# BATT_DISP.net
KiCad netlist of a schematic drawn in EAGLE
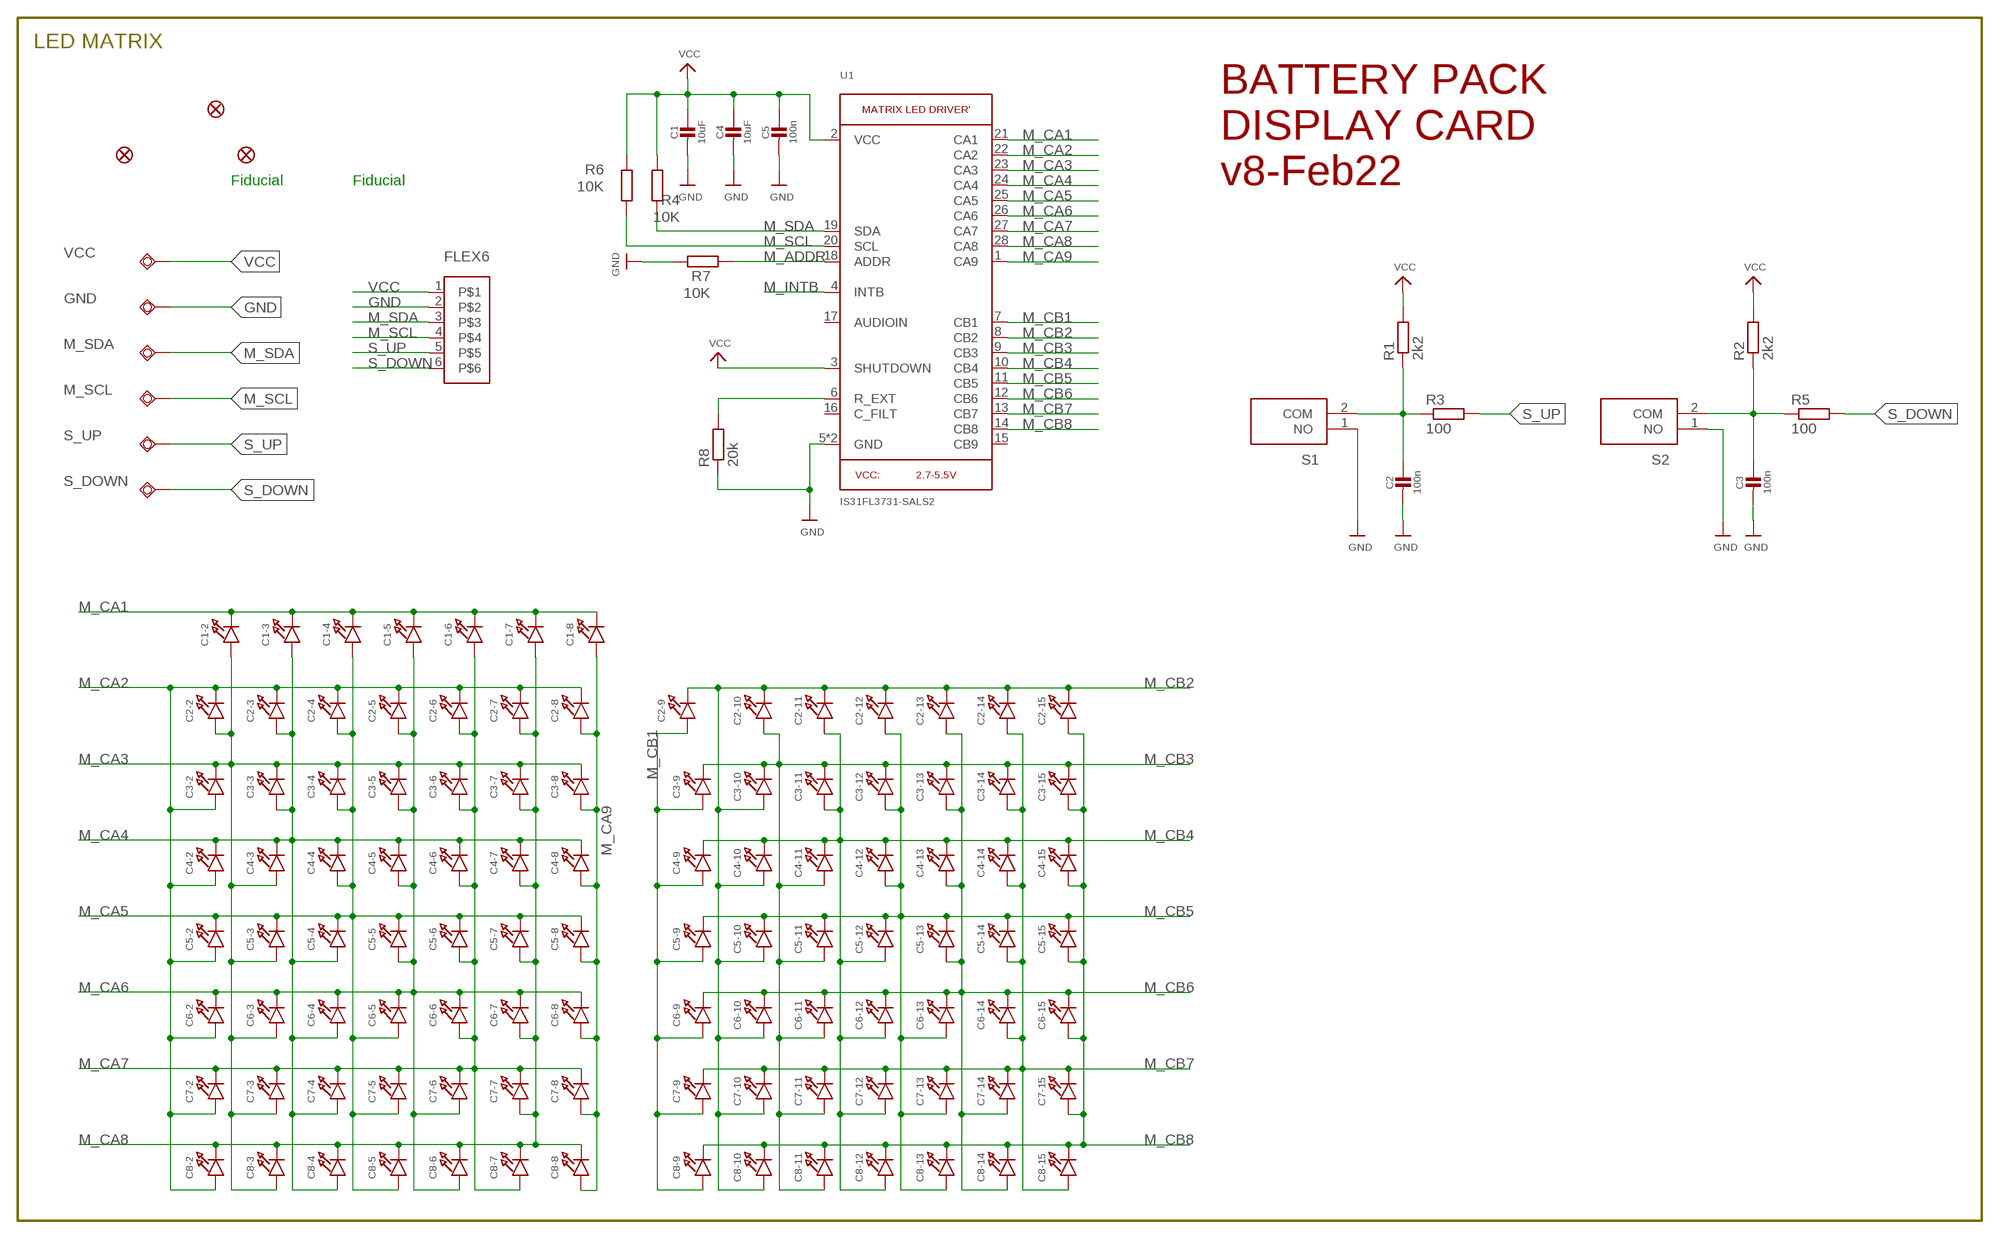
[diagram p0: schematic, sheet 1]

(export (version "E")
  (design (tool "Eeschema 10.0.6"))
  (components
    (comp (ref "C1")
      (value "10uF")
      (footprint "eagle-import:0805-NO")
      (libsource (lib "eagle-import") (part "CAP_CERAMIC0805-NOOUTLINE"))
    )
    (comp (ref "C1-2")
      (value "LED0402_NOOUTLINE")
      (footprint "eagle-import:CHIPLED_0402_NOOUTLINE")
      (libsource (lib "eagle-import") (part "LED0402_NOOUTLINE"))
    )
    (comp (ref "C1-3")
      (value "LED0402_NOOUTLINE")
      (footprint "eagle-import:CHIPLED_0402_NOOUTLINE")
      (libsource (lib "eagle-import") (part "LED0402_NOOUTLINE"))
    )
    (comp (ref "C1-4")
      (value "LED0402_NOOUTLINE")
      (footprint "eagle-import:CHIPLED_0402_NOOUTLINE")
      (libsource (lib "eagle-import") (part "LED0402_NOOUTLINE"))
    )
    (comp (ref "C1-5")
      (value "LED0402_NOOUTLINE")
      (footprint "eagle-import:CHIPLED_0402_NOOUTLINE")
      (libsource (lib "eagle-import") (part "LED0402_NOOUTLINE"))
    )
    (comp (ref "C1-6")
      (value "LED0402_NOOUTLINE")
      (footprint "eagle-import:CHIPLED_0402_NOOUTLINE")
      (libsource (lib "eagle-import") (part "LED0402_NOOUTLINE"))
    )
    (comp (ref "C1-7")
      (value "LED0402_NOOUTLINE")
      (footprint "eagle-import:CHIPLED_0402_NOOUTLINE")
      (libsource (lib "eagle-import") (part "LED0402_NOOUTLINE"))
    )
    (comp (ref "C1-8")
      (value "LED0402_NOOUTLINE")
      (footprint "eagle-import:CHIPLED_0402_NOOUTLINE")
      (libsource (lib "eagle-import") (part "LED0402_NOOUTLINE"))
    )
    (comp (ref "C2")
      (value "100n")
      (footprint "eagle-import:0805-NO")
      (libsource (lib "eagle-import") (part "CAP_CERAMIC0805-NOOUTLINE"))
    )
    (comp (ref "C2-2")
      (value "LED0402_NOOUTLINE")
      (footprint "eagle-import:CHIPLED_0402_NOOUTLINE")
      (libsource (lib "eagle-import") (part "LED0402_NOOUTLINE"))
    )
    (comp (ref "C2-3")
      (value "LED0402_NOOUTLINE")
      (footprint "eagle-import:CHIPLED_0402_NOOUTLINE")
      (libsource (lib "eagle-import") (part "LED0402_NOOUTLINE"))
    )
    (comp (ref "C2-4")
      (value "LED0402_NOOUTLINE")
      (footprint "eagle-import:CHIPLED_0402_NOOUTLINE")
      (libsource (lib "eagle-import") (part "LED0402_NOOUTLINE"))
    )
    (comp (ref "C2-5")
      (value "LED0402_NOOUTLINE")
      (footprint "eagle-import:CHIPLED_0402_NOOUTLINE")
      (libsource (lib "eagle-import") (part "LED0402_NOOUTLINE"))
    )
    (comp (ref "C2-6")
      (value "LED0402_NOOUTLINE")
      (footprint "eagle-import:CHIPLED_0402_NOOUTLINE")
      (libsource (lib "eagle-import") (part "LED0402_NOOUTLINE"))
    )
    (comp (ref "C2-7")
      (value "LED0402_NOOUTLINE")
      (footprint "eagle-import:CHIPLED_0402_NOOUTLINE")
      (libsource (lib "eagle-import") (part "LED0402_NOOUTLINE"))
    )
    (comp (ref "C2-8")
      (value "LED0402_NOOUTLINE")
      (footprint "eagle-import:CHIPLED_0402_NOOUTLINE")
      (libsource (lib "eagle-import") (part "LED0402_NOOUTLINE"))
    )
    (comp (ref "C2-9")
      (value "LED0402_NOOUTLINE")
      (footprint "eagle-import:CHIPLED_0402_NOOUTLINE")
      (libsource (lib "eagle-import") (part "LED0402_NOOUTLINE"))
    )
    (comp (ref "C2-10")
      (value "LED0402_NOOUTLINE")
      (footprint "eagle-import:CHIPLED_0402_NOOUTLINE")
      (libsource (lib "eagle-import") (part "LED0402_NOOUTLINE"))
    )
    (comp (ref "C2-11")
      (value "LED0402_NOOUTLINE")
      (footprint "eagle-import:CHIPLED_0402_NOOUTLINE")
      (libsource (lib "eagle-import") (part "LED0402_NOOUTLINE"))
    )
    (comp (ref "C2-12")
      (value "LED0402_NOOUTLINE")
      (footprint "eagle-import:CHIPLED_0402_NOOUTLINE")
      (libsource (lib "eagle-import") (part "LED0402_NOOUTLINE"))
    )
    (comp (ref "C2-13")
      (value "LED0402_NOOUTLINE")
      (footprint "eagle-import:CHIPLED_0402_NOOUTLINE")
      (libsource (lib "eagle-import") (part "LED0402_NOOUTLINE"))
    )
    (comp (ref "C2-14")
      (value "LED0402_NOOUTLINE")
      (footprint "eagle-import:CHIPLED_0402_NOOUTLINE")
      (libsource (lib "eagle-import") (part "LED0402_NOOUTLINE"))
    )
    (comp (ref "C2-15")
      (value "LED0402_NOOUTLINE")
      (footprint "eagle-import:CHIPLED_0402_NOOUTLINE")
      (libsource (lib "eagle-import") (part "LED0402_NOOUTLINE"))
    )
    (comp (ref "C3")
      (value "100n")
      (footprint "eagle-import:0805-NO")
      (libsource (lib "eagle-import") (part "CAP_CERAMIC0805-NOOUTLINE"))
    )
    (comp (ref "C3-2")
      (value "LED0402_NOOUTLINE")
      (footprint "eagle-import:CHIPLED_0402_NOOUTLINE")
      (libsource (lib "eagle-import") (part "LED0402_NOOUTLINE"))
    )
    (comp (ref "C3-3")
      (value "LED0402_NOOUTLINE")
      (footprint "eagle-import:CHIPLED_0402_NOOUTLINE")
      (libsource (lib "eagle-import") (part "LED0402_NOOUTLINE"))
    )
    (comp (ref "C3-4")
      (value "LED0402_NOOUTLINE")
      (footprint "eagle-import:CHIPLED_0402_NOOUTLINE")
      (libsource (lib "eagle-import") (part "LED0402_NOOUTLINE"))
    )
    (comp (ref "C3-5")
      (value "LED0402_NOOUTLINE")
      (footprint "eagle-import:CHIPLED_0402_NOOUTLINE")
      (libsource (lib "eagle-import") (part "LED0402_NOOUTLINE"))
    )
    (comp (ref "C3-6")
      (value "LED0402_NOOUTLINE")
      (footprint "eagle-import:CHIPLED_0402_NOOUTLINE")
      (libsource (lib "eagle-import") (part "LED0402_NOOUTLINE"))
    )
    (comp (ref "C3-7")
      (value "LED0402_NOOUTLINE")
      (footprint "eagle-import:CHIPLED_0402_NOOUTLINE")
      (libsource (lib "eagle-import") (part "LED0402_NOOUTLINE"))
    )
    (comp (ref "C3-8")
      (value "LED0402_NOOUTLINE")
      (footprint "eagle-import:CHIPLED_0402_NOOUTLINE")
      (libsource (lib "eagle-import") (part "LED0402_NOOUTLINE"))
    )
    (comp (ref "C3-9")
      (value "LED0402_NOOUTLINE")
      (footprint "eagle-import:CHIPLED_0402_NOOUTLINE")
      (libsource (lib "eagle-import") (part "LED0402_NOOUTLINE"))
    )
    (comp (ref "C3-10")
      (value "LED0402_NOOUTLINE")
      (footprint "eagle-import:CHIPLED_0402_NOOUTLINE")
      (libsource (lib "eagle-import") (part "LED0402_NOOUTLINE"))
    )
    (comp (ref "C3-11")
      (value "LED0402_NOOUTLINE")
      (footprint "eagle-import:CHIPLED_0402_NOOUTLINE")
      (libsource (lib "eagle-import") (part "LED0402_NOOUTLINE"))
    )
    (comp (ref "C3-12")
      (value "LED0402_NOOUTLINE")
      (footprint "eagle-import:CHIPLED_0402_NOOUTLINE")
      (libsource (lib "eagle-import") (part "LED0402_NOOUTLINE"))
    )
    (comp (ref "C3-13")
      (value "LED0402_NOOUTLINE")
      (footprint "eagle-import:CHIPLED_0402_NOOUTLINE")
      (libsource (lib "eagle-import") (part "LED0402_NOOUTLINE"))
    )
    (comp (ref "C3-14")
      (value "LED0402_NOOUTLINE")
      (footprint "eagle-import:CHIPLED_0402_NOOUTLINE")
      (libsource (lib "eagle-import") (part "LED0402_NOOUTLINE"))
    )
    (comp (ref "C3-15")
      (value "LED0402_NOOUTLINE")
      (footprint "eagle-import:CHIPLED_0402_NOOUTLINE")
      (libsource (lib "eagle-import") (part "LED0402_NOOUTLINE"))
    )
    (comp (ref "C4")
      (value "10uF")
      (footprint "eagle-import:0805-NO")
      (libsource (lib "eagle-import") (part "CAP_CERAMIC0805-NOOUTLINE"))
    )
    (comp (ref "C4-2")
      (value "LED0402_NOOUTLINE")
      (footprint "eagle-import:CHIPLED_0402_NOOUTLINE")
      (libsource (lib "eagle-import") (part "LED0402_NOOUTLINE"))
    )
    (comp (ref "C4-3")
      (value "LED0402_NOOUTLINE")
      (footprint "eagle-import:CHIPLED_0402_NOOUTLINE")
      (libsource (lib "eagle-import") (part "LED0402_NOOUTLINE"))
    )
    (comp (ref "C4-4")
      (value "LED0402_NOOUTLINE")
      (footprint "eagle-import:CHIPLED_0402_NOOUTLINE")
      (libsource (lib "eagle-import") (part "LED0402_NOOUTLINE"))
    )
    (comp (ref "C4-5")
      (value "LED0402_NOOUTLINE")
      (footprint "eagle-import:CHIPLED_0402_NOOUTLINE")
      (libsource (lib "eagle-import") (part "LED0402_NOOUTLINE"))
    )
    (comp (ref "C4-6")
      (value "LED0402_NOOUTLINE")
      (footprint "eagle-import:CHIPLED_0402_NOOUTLINE")
      (libsource (lib "eagle-import") (part "LED0402_NOOUTLINE"))
    )
    (comp (ref "C4-7")
      (value "LED0402_NOOUTLINE")
      (footprint "eagle-import:CHIPLED_0402_NOOUTLINE")
      (libsource (lib "eagle-import") (part "LED0402_NOOUTLINE"))
    )
    (comp (ref "C4-8")
      (value "LED0402_NOOUTLINE")
      (footprint "eagle-import:CHIPLED_0402_NOOUTLINE")
      (libsource (lib "eagle-import") (part "LED0402_NOOUTLINE"))
    )
    (comp (ref "C4-9")
      (value "LED0402_NOOUTLINE")
      (footprint "eagle-import:CHIPLED_0402_NOOUTLINE")
      (libsource (lib "eagle-import") (part "LED0402_NOOUTLINE"))
    )
    (comp (ref "C4-10")
      (value "LED0402_NOOUTLINE")
      (footprint "eagle-import:CHIPLED_0402_NOOUTLINE")
      (libsource (lib "eagle-import") (part "LED0402_NOOUTLINE"))
    )
    (comp (ref "C4-11")
      (value "LED0402_NOOUTLINE")
      (footprint "eagle-import:CHIPLED_0402_NOOUTLINE")
      (libsource (lib "eagle-import") (part "LED0402_NOOUTLINE"))
    )
    (comp (ref "C4-12")
      (value "LED0402_NOOUTLINE")
      (footprint "eagle-import:CHIPLED_0402_NOOUTLINE")
      (libsource (lib "eagle-import") (part "LED0402_NOOUTLINE"))
    )
    (comp (ref "C4-13")
      (value "LED0402_NOOUTLINE")
      (footprint "eagle-import:CHIPLED_0402_NOOUTLINE")
      (libsource (lib "eagle-import") (part "LED0402_NOOUTLINE"))
    )
    (comp (ref "C4-14")
      (value "LED0402_NOOUTLINE")
      (footprint "eagle-import:CHIPLED_0402_NOOUTLINE")
      (libsource (lib "eagle-import") (part "LED0402_NOOUTLINE"))
    )
    (comp (ref "C4-15")
      (value "LED0402_NOOUTLINE")
      (footprint "eagle-import:CHIPLED_0402_NOOUTLINE")
      (libsource (lib "eagle-import") (part "LED0402_NOOUTLINE"))
    )
    (comp (ref "C5")
      (value "100n")
      (footprint "eagle-import:0805-NO")
      (libsource (lib "eagle-import") (part "CAP_CERAMIC0805-NOOUTLINE"))
    )
    (comp (ref "C5-2")
      (value "LED0402_NOOUTLINE")
      (footprint "eagle-import:CHIPLED_0402_NOOUTLINE")
      (libsource (lib "eagle-import") (part "LED0402_NOOUTLINE"))
    )
    (comp (ref "C5-3")
      (value "LED0402_NOOUTLINE")
      (footprint "eagle-import:CHIPLED_0402_NOOUTLINE")
      (libsource (lib "eagle-import") (part "LED0402_NOOUTLINE"))
    )
    (comp (ref "C5-4")
      (value "LED0402_NOOUTLINE")
      (footprint "eagle-import:CHIPLED_0402_NOOUTLINE")
      (libsource (lib "eagle-import") (part "LED0402_NOOUTLINE"))
    )
    (comp (ref "C5-5")
      (value "LED0402_NOOUTLINE")
      (footprint "eagle-import:CHIPLED_0402_NOOUTLINE")
      (libsource (lib "eagle-import") (part "LED0402_NOOUTLINE"))
    )
    (comp (ref "C5-6")
      (value "LED0402_NOOUTLINE")
      (footprint "eagle-import:CHIPLED_0402_NOOUTLINE")
      (libsource (lib "eagle-import") (part "LED0402_NOOUTLINE"))
    )
    (comp (ref "C5-7")
      (value "LED0402_NOOUTLINE")
      (footprint "eagle-import:CHIPLED_0402_NOOUTLINE")
      (libsource (lib "eagle-import") (part "LED0402_NOOUTLINE"))
    )
    (comp (ref "C5-8")
      (value "LED0402_NOOUTLINE")
      (footprint "eagle-import:CHIPLED_0402_NOOUTLINE")
      (libsource (lib "eagle-import") (part "LED0402_NOOUTLINE"))
    )
    (comp (ref "C5-9")
      (value "LED0402_NOOUTLINE")
      (footprint "eagle-import:CHIPLED_0402_NOOUTLINE")
      (libsource (lib "eagle-import") (part "LED0402_NOOUTLINE"))
    )
    (comp (ref "C5-10")
      (value "LED0402_NOOUTLINE")
      (footprint "eagle-import:CHIPLED_0402_NOOUTLINE")
      (libsource (lib "eagle-import") (part "LED0402_NOOUTLINE"))
    )
    (comp (ref "C5-11")
      (value "LED0402_NOOUTLINE")
      (footprint "eagle-import:CHIPLED_0402_NOOUTLINE")
      (libsource (lib "eagle-import") (part "LED0402_NOOUTLINE"))
    )
    (comp (ref "C5-12")
      (value "LED0402_NOOUTLINE")
      (footprint "eagle-import:CHIPLED_0402_NOOUTLINE")
      (libsource (lib "eagle-import") (part "LED0402_NOOUTLINE"))
    )
    (comp (ref "C5-13")
      (value "LED0402_NOOUTLINE")
      (footprint "eagle-import:CHIPLED_0402_NOOUTLINE")
      (libsource (lib "eagle-import") (part "LED0402_NOOUTLINE"))
    )
    (comp (ref "C5-14")
      (value "LED0402_NOOUTLINE")
      (footprint "eagle-import:CHIPLED_0402_NOOUTLINE")
      (libsource (lib "eagle-import") (part "LED0402_NOOUTLINE"))
    )
    (comp (ref "C5-15")
      (value "LED0402_NOOUTLINE")
      (footprint "eagle-import:CHIPLED_0402_NOOUTLINE")
      (libsource (lib "eagle-import") (part "LED0402_NOOUTLINE"))
    )
    (comp (ref "C6-2")
      (value "LED0402_NOOUTLINE")
      (footprint "eagle-import:CHIPLED_0402_NOOUTLINE")
      (libsource (lib "eagle-import") (part "LED0402_NOOUTLINE"))
    )
    (comp (ref "C6-3")
      (value "LED0402_NOOUTLINE")
      (footprint "eagle-import:CHIPLED_0402_NOOUTLINE")
      (libsource (lib "eagle-import") (part "LED0402_NOOUTLINE"))
    )
    (comp (ref "C6-4")
      (value "LED0402_NOOUTLINE")
      (footprint "eagle-import:CHIPLED_0402_NOOUTLINE")
      (libsource (lib "eagle-import") (part "LED0402_NOOUTLINE"))
    )
    (comp (ref "C6-5")
      (value "LED0402_NOOUTLINE")
      (footprint "eagle-import:CHIPLED_0402_NOOUTLINE")
      (libsource (lib "eagle-import") (part "LED0402_NOOUTLINE"))
    )
    (comp (ref "C6-6")
      (value "LED0402_NOOUTLINE")
      (footprint "eagle-import:CHIPLED_0402_NOOUTLINE")
      (libsource (lib "eagle-import") (part "LED0402_NOOUTLINE"))
    )
    (comp (ref "C6-7")
      (value "LED0402_NOOUTLINE")
      (footprint "eagle-import:CHIPLED_0402_NOOUTLINE")
      (libsource (lib "eagle-import") (part "LED0402_NOOUTLINE"))
    )
    (comp (ref "C6-8")
      (value "LED0402_NOOUTLINE")
      (footprint "eagle-import:CHIPLED_0402_NOOUTLINE")
      (libsource (lib "eagle-import") (part "LED0402_NOOUTLINE"))
    )
    (comp (ref "C6-9")
      (value "LED0402_NOOUTLINE")
      (footprint "eagle-import:CHIPLED_0402_NOOUTLINE")
      (libsource (lib "eagle-import") (part "LED0402_NOOUTLINE"))
    )
    (comp (ref "C6-10")
      (value "LED0402_NOOUTLINE")
      (footprint "eagle-import:CHIPLED_0402_NOOUTLINE")
      (libsource (lib "eagle-import") (part "LED0402_NOOUTLINE"))
    )
    (comp (ref "C6-11")
      (value "LED0402_NOOUTLINE")
      (footprint "eagle-import:CHIPLED_0402_NOOUTLINE")
      (libsource (lib "eagle-import") (part "LED0402_NOOUTLINE"))
    )
    (comp (ref "C6-12")
      (value "LED0402_NOOUTLINE")
      (footprint "eagle-import:CHIPLED_0402_NOOUTLINE")
      (libsource (lib "eagle-import") (part "LED0402_NOOUTLINE"))
    )
    (comp (ref "C6-13")
      (value "LED0402_NOOUTLINE")
      (footprint "eagle-import:CHIPLED_0402_NOOUTLINE")
      (libsource (lib "eagle-import") (part "LED0402_NOOUTLINE"))
    )
    (comp (ref "C6-14")
      (value "LED0402_NOOUTLINE")
      (footprint "eagle-import:CHIPLED_0402_NOOUTLINE")
      (libsource (lib "eagle-import") (part "LED0402_NOOUTLINE"))
    )
    (comp (ref "C6-15")
      (value "LED0402_NOOUTLINE")
      (footprint "eagle-import:CHIPLED_0402_NOOUTLINE")
      (libsource (lib "eagle-import") (part "LED0402_NOOUTLINE"))
    )
    (comp (ref "C7-2")
      (value "LED0402_NOOUTLINE")
      (footprint "eagle-import:CHIPLED_0402_NOOUTLINE")
      (libsource (lib "eagle-import") (part "LED0402_NOOUTLINE"))
    )
    (comp (ref "C7-3")
      (value "LED0402_NOOUTLINE")
      (footprint "eagle-import:CHIPLED_0402_NOOUTLINE")
      (libsource (lib "eagle-import") (part "LED0402_NOOUTLINE"))
    )
    (comp (ref "C7-4")
      (value "LED0402_NOOUTLINE")
      (footprint "eagle-import:CHIPLED_0402_NOOUTLINE")
      (libsource (lib "eagle-import") (part "LED0402_NOOUTLINE"))
    )
    (comp (ref "C7-5")
      (value "LED0402_NOOUTLINE")
      (footprint "eagle-import:CHIPLED_0402_NOOUTLINE")
      (libsource (lib "eagle-import") (part "LED0402_NOOUTLINE"))
    )
    (comp (ref "C7-6")
      (value "LED0402_NOOUTLINE")
      (footprint "eagle-import:CHIPLED_0402_NOOUTLINE")
      (libsource (lib "eagle-import") (part "LED0402_NOOUTLINE"))
    )
    (comp (ref "C7-7")
      (value "LED0402_NOOUTLINE")
      (footprint "eagle-import:CHIPLED_0402_NOOUTLINE")
      (libsource (lib "eagle-import") (part "LED0402_NOOUTLINE"))
    )
    (comp (ref "C7-8")
      (value "LED0402_NOOUTLINE")
      (footprint "eagle-import:CHIPLED_0402_NOOUTLINE")
      (libsource (lib "eagle-import") (part "LED0402_NOOUTLINE"))
    )
    (comp (ref "C7-9")
      (value "LED0402_NOOUTLINE")
      (footprint "eagle-import:CHIPLED_0402_NOOUTLINE")
      (libsource (lib "eagle-import") (part "LED0402_NOOUTLINE"))
    )
    (comp (ref "C7-10")
      (value "LED0402_NOOUTLINE")
      (footprint "eagle-import:CHIPLED_0402_NOOUTLINE")
      (libsource (lib "eagle-import") (part "LED0402_NOOUTLINE"))
    )
    (comp (ref "C7-11")
      (value "LED0402_NOOUTLINE")
      (footprint "eagle-import:CHIPLED_0402_NOOUTLINE")
      (libsource (lib "eagle-import") (part "LED0402_NOOUTLINE"))
    )
    (comp (ref "C7-12")
      (value "LED0402_NOOUTLINE")
      (footprint "eagle-import:CHIPLED_0402_NOOUTLINE")
      (libsource (lib "eagle-import") (part "LED0402_NOOUTLINE"))
    )
    (comp (ref "C7-13")
      (value "LED0402_NOOUTLINE")
      (footprint "eagle-import:CHIPLED_0402_NOOUTLINE")
      (libsource (lib "eagle-import") (part "LED0402_NOOUTLINE"))
    )
    (comp (ref "C7-14")
      (value "LED0402_NOOUTLINE")
      (footprint "eagle-import:CHIPLED_0402_NOOUTLINE")
      (libsource (lib "eagle-import") (part "LED0402_NOOUTLINE"))
    )
    (comp (ref "C7-15")
      (value "LED0402_NOOUTLINE")
      (footprint "eagle-import:CHIPLED_0402_NOOUTLINE")
      (libsource (lib "eagle-import") (part "LED0402_NOOUTLINE"))
    )
    (comp (ref "C8-2")
      (value "LED0402_NOOUTLINE")
      (footprint "eagle-import:CHIPLED_0402_NOOUTLINE")
      (libsource (lib "eagle-import") (part "LED0402_NOOUTLINE"))
    )
    (comp (ref "C8-3")
      (value "LED0402_NOOUTLINE")
      (footprint "eagle-import:CHIPLED_0402_NOOUTLINE")
      (libsource (lib "eagle-import") (part "LED0402_NOOUTLINE"))
    )
    (comp (ref "C8-4")
      (value "LED0402_NOOUTLINE")
      (footprint "eagle-import:CHIPLED_0402_NOOUTLINE")
      (libsource (lib "eagle-import") (part "LED0402_NOOUTLINE"))
    )
    (comp (ref "C8-5")
      (value "LED0402_NOOUTLINE")
      (footprint "eagle-import:CHIPLED_0402_NOOUTLINE")
      (libsource (lib "eagle-import") (part "LED0402_NOOUTLINE"))
    )
    (comp (ref "C8-6")
      (value "LED0402_NOOUTLINE")
      (footprint "eagle-import:CHIPLED_0402_NOOUTLINE")
      (libsource (lib "eagle-import") (part "LED0402_NOOUTLINE"))
    )
    (comp (ref "C8-7")
      (value "LED0402_NOOUTLINE")
      (footprint "eagle-import:CHIPLED_0402_NOOUTLINE")
      (libsource (lib "eagle-import") (part "LED0402_NOOUTLINE"))
    )
    (comp (ref "C8-8")
      (value "LED0402_NOOUTLINE")
      (footprint "eagle-import:CHIPLED_0402_NOOUTLINE")
      (libsource (lib "eagle-import") (part "LED0402_NOOUTLINE"))
    )
    (comp (ref "C8-9")
      (value "LED0402_NOOUTLINE")
      (footprint "eagle-import:CHIPLED_0402_NOOUTLINE")
      (libsource (lib "eagle-import") (part "LED0402_NOOUTLINE"))
    )
    (comp (ref "C8-10")
      (value "LED0402_NOOUTLINE")
      (footprint "eagle-import:CHIPLED_0402_NOOUTLINE")
      (libsource (lib "eagle-import") (part "LED0402_NOOUTLINE"))
    )
    (comp (ref "C8-11")
      (value "LED0402_NOOUTLINE")
      (footprint "eagle-import:CHIPLED_0402_NOOUTLINE")
      (libsource (lib "eagle-import") (part "LED0402_NOOUTLINE"))
    )
    (comp (ref "C8-12")
      (value "LED0402_NOOUTLINE")
      (footprint "eagle-import:CHIPLED_0402_NOOUTLINE")
      (libsource (lib "eagle-import") (part "LED0402_NOOUTLINE"))
    )
    (comp (ref "C8-13")
      (value "LED0402_NOOUTLINE")
      (footprint "eagle-import:CHIPLED_0402_NOOUTLINE")
      (libsource (lib "eagle-import") (part "LED0402_NOOUTLINE"))
    )
    (comp (ref "C8-14")
      (value "LED0402_NOOUTLINE")
      (footprint "eagle-import:CHIPLED_0402_NOOUTLINE")
      (libsource (lib "eagle-import") (part "LED0402_NOOUTLINE"))
    )
    (comp (ref "C8-15")
      (value "LED0402_NOOUTLINE")
      (footprint "eagle-import:CHIPLED_0402_NOOUTLINE")
      (libsource (lib "eagle-import") (part "LED0402_NOOUTLINE"))
    )
    (comp (ref "FD1")
      (value "FIDUCIALUFIDUCIAL")
      (footprint "eagle-import:FIDUCIAL-MICRO")
      (libsource (lib "eagle-import") (part "FIDUCIALUFIDUCIAL"))
    )
    (comp (ref "FD2")
      (value "FIDUCIAL\"\"")
      (footprint "eagle-import:FIDUCIAL_1MM")
      (libsource (lib "eagle-import") (part "FIDUCIAL{dblquote}{dblquote}"))
    )
    (comp (ref "FD3")
      (value "FIDUCIAL\"\"")
      (footprint "eagle-import:FIDUCIAL_1MM")
      (libsource (lib "eagle-import") (part "FIDUCIAL{dblquote}{dblquote}"))
    )
    (comp (ref "GND")
      (value "TESTPAD_TPSQB1,27")
      (footprint "eagle-import:TESTPAD_B1,27")
      (libsource (lib "eagle-import") (part "TESTPAD_TPSQB1,27"))
    )
    (comp (ref "K1")
      (value "FLEX6")
      (footprint "eagle-import:FLEX6")
      (libsource (lib "eagle-import") (part "FLEX6"))
    )
    (comp (ref "M_SCL")
      (value "TESTPAD_TPSQB1,27")
      (footprint "eagle-import:TESTPAD_B1,27")
      (libsource (lib "eagle-import") (part "TESTPAD_TPSQB1,27"))
    )
    (comp (ref "M_SDA")
      (value "TESTPAD_TPSQB1,27")
      (footprint "eagle-import:TESTPAD_B1,27")
      (libsource (lib "eagle-import") (part "TESTPAD_TPSQB1,27"))
    )
    (comp (ref "R1")
      (value "2k2")
      (footprint "eagle-import:R0603")
      (libsource (lib "eagle-import") (part "R-EU_R0603"))
    )
    (comp (ref "R2")
      (value "2k2")
      (footprint "eagle-import:R0603")
      (libsource (lib "eagle-import") (part "R-EU_R0603"))
    )
    (comp (ref "R3")
      (value "100")
      (footprint "eagle-import:R0603")
      (libsource (lib "eagle-import") (part "R-EU_R0603"))
    )
    (comp (ref "R4")
      (value "10K")
      (footprint "eagle-import:R0603")
      (libsource (lib "eagle-import") (part "R-EU_R0603"))
    )
    (comp (ref "R5")
      (value "100")
      (footprint "eagle-import:R0603")
      (libsource (lib "eagle-import") (part "R-EU_R0603"))
    )
    (comp (ref "R6")
      (value "10K")
      (footprint "eagle-import:R0603")
      (libsource (lib "eagle-import") (part "R-EU_R0603"))
    )
    (comp (ref "R7")
      (value "10K")
      (footprint "eagle-import:R0603")
      (libsource (lib "eagle-import") (part "R-EU_R0603"))
    )
    (comp (ref "R8")
      (value "20k")
      (footprint "eagle-import:R0603")
      (libsource (lib "eagle-import") (part "R-EU_R0603"))
    )
    (comp (ref "S1")
      (value "KXT311LHS")
      (footprint "eagle-import:KXT311LHS")
      (fields (field (name "MOUSER_PART_NUMBER") "611-KXT311LHS"))
      (libsource (lib "eagle-import") (part "KXT311LHS"))
    )
    (comp (ref "S2")
      (value "KXT311LHS")
      (footprint "eagle-import:KXT311LHS")
      (fields (field (name "MOUSER_PART_NUMBER") "611-KXT311LHS"))
      (libsource (lib "eagle-import") (part "KXT311LHS"))
    )
    (comp (ref "S_DOWN")
      (value "TESTPAD_TPSQB1,27")
      (footprint "eagle-import:TESTPAD_B1,27")
      (libsource (lib "eagle-import") (part "TESTPAD_TPSQB1,27"))
    )
    (comp (ref "S_UP")
      (value "TESTPAD_TPSQB1,27")
      (footprint "eagle-import:TESTPAD_B1,27")
      (libsource (lib "eagle-import") (part "TESTPAD_TPSQB1,27"))
    )
    (comp (ref "U1")
      (value "IS31FL3731-SALS2")
      (footprint "eagle-import:QFN28_4MM_0.4MM")
      (libsource (lib "eagle-import") (part "IS31FL3731QFN"))
    )
    (comp (ref "VCC")
      (value "TESTPAD_TPSQB1,27")
      (footprint "eagle-import:TESTPAD_B1,27")
      (libsource (lib "eagle-import") (part "TESTPAD_TPSQB1,27"))
    )
  )
  (nets
    (net (code "1") (name "/M_ADDR") (class "Default")
      (node (ref "R7") (pin "1") (pinfunction "1_1") (pintype "passive"))
      (node (ref "U1") (pin "18") (pinfunction "ADDR_18") (pintype "bidirectional"))
    )
    (net (code "2") (name "/M_CA1") (class "Default")
      (node (ref "C1-2") (pin "C") (pinfunction "C_C") (pintype "passive"))
      (node (ref "C1-3") (pin "C") (pinfunction "C_C") (pintype "passive"))
      (node (ref "C1-4") (pin "C") (pinfunction "C_C") (pintype "passive"))
      (node (ref "C1-5") (pin "C") (pinfunction "C_C") (pintype "passive"))
      (node (ref "C1-6") (pin "C") (pinfunction "C_C") (pintype "passive"))
      (node (ref "C1-7") (pin "C") (pinfunction "C_C") (pintype "passive"))
      (node (ref "C1-8") (pin "C") (pinfunction "C_C") (pintype "passive"))
      (node (ref "U1") (pin "21") (pinfunction "CA1_21") (pintype "bidirectional"))
    )
    (net (code "3") (name "/M_CA2") (class "Default")
      (node (ref "C2-2") (pin "C") (pinfunction "C_C") (pintype "passive"))
      (node (ref "C2-3") (pin "C") (pinfunction "C_C") (pintype "passive"))
      (node (ref "C2-4") (pin "C") (pinfunction "C_C") (pintype "passive"))
      (node (ref "C2-5") (pin "C") (pinfunction "C_C") (pintype "passive"))
      (node (ref "C2-6") (pin "C") (pinfunction "C_C") (pintype "passive"))
      (node (ref "C2-7") (pin "C") (pinfunction "C_C") (pintype "passive"))
      (node (ref "C2-8") (pin "C") (pinfunction "C_C") (pintype "passive"))
      (node (ref "C3-2") (pin "A") (pinfunction "A_A") (pintype "passive"))
      (node (ref "C4-2") (pin "A") (pinfunction "A_A") (pintype "passive"))
      (node (ref "C5-2") (pin "A") (pinfunction "A_A") (pintype "passive"))
      (node (ref "C6-2") (pin "A") (pinfunction "A_A") (pintype "passive"))
      (node (ref "C7-2") (pin "A") (pinfunction "A_A") (pintype "passive"))
      (node (ref "C8-2") (pin "A") (pinfunction "A_A") (pintype "passive"))
      (node (ref "U1") (pin "22") (pinfunction "CA2_22") (pintype "bidirectional"))
    )
    (net (code "4") (name "/M_CA3") (class "Default")
      (node (ref "C1-2") (pin "A") (pinfunction "A_A") (pintype "passive"))
      (node (ref "C2-2") (pin "A") (pinfunction "A_A") (pintype "passive"))
      (node (ref "C3-2") (pin "C") (pinfunction "C_C") (pintype "passive"))
      (node (ref "C3-3") (pin "C") (pinfunction "C_C") (pintype "passive"))
      (node (ref "C3-4") (pin "C") (pinfunction "C_C") (pintype "passive"))
      (node (ref "C3-5") (pin "C") (pinfunction "C_C") (pintype "passive"))
      (node (ref "C3-6") (pin "C") (pinfunction "C_C") (pintype "passive"))
      (node (ref "C3-7") (pin "C") (pinfunction "C_C") (pintype "passive"))
      (node (ref "C3-8") (pin "C") (pinfunction "C_C") (pintype "passive"))
      (node (ref "C4-3") (pin "A") (pinfunction "A_A") (pintype "passive"))
      (node (ref "C5-3") (pin "A") (pinfunction "A_A") (pintype "passive"))
      (node (ref "C6-3") (pin "A") (pinfunction "A_A") (pintype "passive"))
      (node (ref "C7-3") (pin "A") (pinfunction "A_A") (pintype "passive"))
      (node (ref "C8-3") (pin "A") (pinfunction "A_A") (pintype "passive"))
      (node (ref "U1") (pin "23") (pinfunction "CA3_23") (pintype "bidirectional"))
    )
    (net (code "5") (name "/M_CA4") (class "Default")
      (node (ref "C1-3") (pin "A") (pinfunction "A_A") (pintype "passive"))
      (node (ref "C2-3") (pin "A") (pinfunction "A_A") (pintype "passive"))
      (node (ref "C3-3") (pin "A") (pinfunction "A_A") (pintype "passive"))
      (node (ref "C4-2") (pin "C") (pinfunction "C_C") (pintype "passive"))
      (node (ref "C4-3") (pin "C") (pinfunction "C_C") (pintype "passive"))
      (node (ref "C4-4") (pin "C") (pinfunction "C_C") (pintype "passive"))
      (node (ref "C4-5") (pin "C") (pinfunction "C_C") (pintype "passive"))
      (node (ref "C4-6") (pin "C") (pinfunction "C_C") (pintype "passive"))
      (node (ref "C4-7") (pin "C") (pinfunction "C_C") (pintype "passive"))
      (node (ref "C4-8") (pin "C") (pinfunction "C_C") (pintype "passive"))
      (node (ref "C5-4") (pin "A") (pinfunction "A_A") (pintype "passive"))
      (node (ref "C6-4") (pin "A") (pinfunction "A_A") (pintype "passive"))
      (node (ref "C7-4") (pin "A") (pinfunction "A_A") (pintype "passive"))
      (node (ref "C8-4") (pin "A") (pinfunction "A_A") (pintype "passive"))
      (node (ref "U1") (pin "24") (pinfunction "CA4_24") (pintype "bidirectional"))
    )
    (net (code "6") (name "/M_CA5") (class "Default")
      (node (ref "C1-4") (pin "A") (pinfunction "A_A") (pintype "passive"))
      (node (ref "C2-4") (pin "A") (pinfunction "A_A") (pintype "passive"))
      (node (ref "C3-4") (pin "A") (pinfunction "A_A") (pintype "passive"))
      (node (ref "C4-4") (pin "A") (pinfunction "A_A") (pintype "passive"))
      (node (ref "C5-2") (pin "C") (pinfunction "C_C") (pintype "passive"))
      (node (ref "C5-3") (pin "C") (pinfunction "C_C") (pintype "passive"))
      (node (ref "C5-4") (pin "C") (pinfunction "C_C") (pintype "passive"))
      (node (ref "C5-5") (pin "C") (pinfunction "C_C") (pintype "passive"))
      (node (ref "C5-6") (pin "C") (pinfunction "C_C") (pintype "passive"))
      (node (ref "C5-7") (pin "C") (pinfunction "C_C") (pintype "passive"))
      (node (ref "C5-8") (pin "C") (pinfunction "C_C") (pintype "passive"))
      (node (ref "C6-5") (pin "A") (pinfunction "A_A") (pintype "passive"))
      (node (ref "C7-5") (pin "A") (pinfunction "A_A") (pintype "passive"))
      (node (ref "C8-5") (pin "A") (pinfunction "A_A") (pintype "passive"))
      (node (ref "U1") (pin "25") (pinfunction "CA5_25") (pintype "bidirectional"))
    )
    (net (code "7") (name "/M_CA6") (class "Default")
      (node (ref "C1-5") (pin "A") (pinfunction "A_A") (pintype "passive"))
      (node (ref "C2-5") (pin "A") (pinfunction "A_A") (pintype "passive"))
      (node (ref "C3-5") (pin "A") (pinfunction "A_A") (pintype "passive"))
      (node (ref "C4-5") (pin "A") (pinfunction "A_A") (pintype "passive"))
      (node (ref "C5-5") (pin "A") (pinfunction "A_A") (pintype "passive"))
      (node (ref "C6-2") (pin "C") (pinfunction "C_C") (pintype "passive"))
      (node (ref "C6-3") (pin "C") (pinfunction "C_C") (pintype "passive"))
      (node (ref "C6-4") (pin "C") (pinfunction "C_C") (pintype "passive"))
      (node (ref "C6-5") (pin "C") (pinfunction "C_C") (pintype "passive"))
      (node (ref "C6-6") (pin "C") (pinfunction "C_C") (pintype "passive"))
      (node (ref "C6-7") (pin "C") (pinfunction "C_C") (pintype "passive"))
      (node (ref "C6-8") (pin "C") (pinfunction "C_C") (pintype "passive"))
      (node (ref "C7-6") (pin "A") (pinfunction "A_A") (pintype "passive"))
      (node (ref "C8-6") (pin "A") (pinfunction "A_A") (pintype "passive"))
      (node (ref "U1") (pin "26") (pinfunction "CA6_26") (pintype "bidirectional"))
    )
    (net (code "8") (name "/M_CA7") (class "Default")
      (node (ref "C1-6") (pin "A") (pinfunction "A_A") (pintype "passive"))
      (node (ref "C2-6") (pin "A") (pinfunction "A_A") (pintype "passive"))
      (node (ref "C3-6") (pin "A") (pinfunction "A_A") (pintype "passive"))
      (node (ref "C4-6") (pin "A") (pinfunction "A_A") (pintype "passive"))
      (node (ref "C5-6") (pin "A") (pinfunction "A_A") (pintype "passive"))
      (node (ref "C6-6") (pin "A") (pinfunction "A_A") (pintype "passive"))
      (node (ref "C7-2") (pin "C") (pinfunction "C_C") (pintype "passive"))
      (node (ref "C7-3") (pin "C") (pinfunction "C_C") (pintype "passive"))
      (node (ref "C7-4") (pin "C") (pinfunction "C_C") (pintype "passive"))
      (node (ref "C7-5") (pin "C") (pinfunction "C_C") (pintype "passive"))
      (node (ref "C7-6") (pin "C") (pinfunction "C_C") (pintype "passive"))
      (node (ref "C7-7") (pin "C") (pinfunction "C_C") (pintype "passive"))
      (node (ref "C7-8") (pin "C") (pinfunction "C_C") (pintype "passive"))
      (node (ref "C8-7") (pin "A") (pinfunction "A_A") (pintype "passive"))
      (node (ref "U1") (pin "27") (pinfunction "CA7_27") (pintype "bidirectional"))
    )
    (net (code "9") (name "/M_CA8") (class "Default")
      (node (ref "C1-7") (pin "A") (pinfunction "A_A") (pintype "passive"))
      (node (ref "C2-7") (pin "A") (pinfunction "A_A") (pintype "passive"))
      (node (ref "C3-7") (pin "A") (pinfunction "A_A") (pintype "passive"))
      (node (ref "C4-7") (pin "A") (pinfunction "A_A") (pintype "passive"))
      (node (ref "C5-7") (pin "A") (pinfunction "A_A") (pintype "passive"))
      (node (ref "C6-7") (pin "A") (pinfunction "A_A") (pintype "passive"))
      (node (ref "C7-7") (pin "A") (pinfunction "A_A") (pintype "passive"))
      (node (ref "C8-2") (pin "C") (pinfunction "C_C") (pintype "passive"))
      (node (ref "C8-3") (pin "C") (pinfunction "C_C") (pintype "passive"))
      (node (ref "C8-4") (pin "C") (pinfunction "C_C") (pintype "passive"))
      (node (ref "C8-5") (pin "C") (pinfunction "C_C") (pintype "passive"))
      (node (ref "C8-6") (pin "C") (pinfunction "C_C") (pintype "passive"))
      (node (ref "C8-7") (pin "C") (pinfunction "C_C") (pintype "passive"))
      (node (ref "C8-8") (pin "C") (pinfunction "C_C") (pintype "passive"))
      (node (ref "U1") (pin "28") (pinfunction "CA8_28") (pintype "bidirectional"))
    )
    (net (code "10") (name "/M_CA9") (class "Default")
      (node (ref "C1-8") (pin "A") (pinfunction "A_A") (pintype "passive"))
      (node (ref "C2-8") (pin "A") (pinfunction "A_A") (pintype "passive"))
      (node (ref "C3-8") (pin "A") (pinfunction "A_A") (pintype "passive"))
      (node (ref "C4-8") (pin "A") (pinfunction "A_A") (pintype "passive"))
      (node (ref "C5-8") (pin "A") (pinfunction "A_A") (pintype "passive"))
      (node (ref "C6-8") (pin "A") (pinfunction "A_A") (pintype "passive"))
      (node (ref "C7-8") (pin "A") (pinfunction "A_A") (pintype "passive"))
      (node (ref "C8-8") (pin "A") (pinfunction "A_A") (pintype "passive"))
      (node (ref "U1") (pin "1") (pinfunction "CA9_1") (pintype "bidirectional"))
    )
    (net (code "11") (name "/M_CB1") (class "Default")
      (node (ref "C2-9") (pin "A") (pinfunction "A_A") (pintype "passive"))
      (node (ref "C3-9") (pin "A") (pinfunction "A_A") (pintype "passive"))
      (node (ref "C4-9") (pin "A") (pinfunction "A_A") (pintype "passive"))
      (node (ref "C5-9") (pin "A") (pinfunction "A_A") (pintype "passive"))
      (node (ref "C6-9") (pin "A") (pinfunction "A_A") (pintype "passive"))
      (node (ref "C7-9") (pin "A") (pinfunction "A_A") (pintype "passive"))
      (node (ref "C8-9") (pin "A") (pinfunction "A_A") (pintype "passive"))
      (node (ref "U1") (pin "7") (pinfunction "CB1_7") (pintype "bidirectional"))
    )
    (net (code "12") (name "/M_CB2") (class "Default")
      (node (ref "C2-10") (pin "C") (pinfunction "C_C") (pintype "passive"))
      (node (ref "C2-11") (pin "C") (pinfunction "C_C") (pintype "passive"))
      (node (ref "C2-12") (pin "C") (pinfunction "C_C") (pintype "passive"))
      (node (ref "C2-13") (pin "C") (pinfunction "C_C") (pintype "passive"))
      (node (ref "C2-14") (pin "C") (pinfunction "C_C") (pintype "passive"))
      (node (ref "C2-15") (pin "C") (pinfunction "C_C") (pintype "passive"))
      (node (ref "C2-9") (pin "C") (pinfunction "C_C") (pintype "passive"))
      (node (ref "C3-10") (pin "A") (pinfunction "A_A") (pintype "passive"))
      (node (ref "C4-10") (pin "A") (pinfunction "A_A") (pintype "passive"))
      (node (ref "C5-10") (pin "A") (pinfunction "A_A") (pintype "passive"))
      (node (ref "C6-10") (pin "A") (pinfunction "A_A") (pintype "passive"))
      (node (ref "C7-10") (pin "A") (pinfunction "A_A") (pintype "passive"))
      (node (ref "C8-10") (pin "A") (pinfunction "A_A") (pintype "passive"))
      (node (ref "U1") (pin "8") (pinfunction "CB2_8") (pintype "bidirectional"))
    )
    (net (code "13") (name "/M_CB3") (class "Default")
      (node (ref "C2-10") (pin "A") (pinfunction "A_A") (pintype "passive"))
      (node (ref "C3-10") (pin "C") (pinfunction "C_C") (pintype "passive"))
      (node (ref "C3-11") (pin "C") (pinfunction "C_C") (pintype "passive"))
      (node (ref "C3-12") (pin "C") (pinfunction "C_C") (pintype "passive"))
      (node (ref "C3-13") (pin "C") (pinfunction "C_C") (pintype "passive"))
      (node (ref "C3-14") (pin "C") (pinfunction "C_C") (pintype "passive"))
      (node (ref "C3-15") (pin "C") (pinfunction "C_C") (pintype "passive"))
      (node (ref "C3-9") (pin "C") (pinfunction "C_C") (pintype "passive"))
      (node (ref "C4-11") (pin "A") (pinfunction "A_A") (pintype "passive"))
      (node (ref "C5-11") (pin "A") (pinfunction "A_A") (pintype "passive"))
      (node (ref "C6-11") (pin "A") (pinfunction "A_A") (pintype "passive"))
      (node (ref "C7-11") (pin "A") (pinfunction "A_A") (pintype "passive"))
      (node (ref "C8-11") (pin "A") (pinfunction "A_A") (pintype "passive"))
      (node (ref "U1") (pin "9") (pinfunction "CB3_9") (pintype "bidirectional"))
    )
    (net (code "14") (name "/M_CB4") (class "Default")
      (node (ref "C2-11") (pin "A") (pinfunction "A_A") (pintype "passive"))
      (node (ref "C3-11") (pin "A") (pinfunction "A_A") (pintype "passive"))
      (node (ref "C4-10") (pin "C") (pinfunction "C_C") (pintype "passive"))
      (node (ref "C4-11") (pin "C") (pinfunction "C_C") (pintype "passive"))
      (node (ref "C4-12") (pin "C") (pinfunction "C_C") (pintype "passive"))
      (node (ref "C4-13") (pin "C") (pinfunction "C_C") (pintype "passive"))
      (node (ref "C4-14") (pin "C") (pinfunction "C_C") (pintype "passive"))
      (node (ref "C4-15") (pin "C") (pinfunction "C_C") (pintype "passive"))
      (node (ref "C4-9") (pin "C") (pinfunction "C_C") (pintype "passive"))
      (node (ref "C5-12") (pin "A") (pinfunction "A_A") (pintype "passive"))
      (node (ref "C6-12") (pin "A") (pinfunction "A_A") (pintype "passive"))
      (node (ref "C7-12") (pin "A") (pinfunction "A_A") (pintype "passive"))
      (node (ref "C8-12") (pin "A") (pinfunction "A_A") (pintype "passive"))
      (node (ref "U1") (pin "10") (pinfunction "CB4_10") (pintype "bidirectional"))
    )
    (net (code "15") (name "/M_CB5") (class "Default")
      (node (ref "C2-12") (pin "A") (pinfunction "A_A") (pintype "passive"))
      (node (ref "C3-12") (pin "A") (pinfunction "A_A") (pintype "passive"))
      (node (ref "C4-12") (pin "A") (pinfunction "A_A") (pintype "passive"))
      (node (ref "C5-10") (pin "C") (pinfunction "C_C") (pintype "passive"))
      (node (ref "C5-11") (pin "C") (pinfunction "C_C") (pintype "passive"))
      (node (ref "C5-12") (pin "C") (pinfunction "C_C") (pintype "passive"))
      (node (ref "C5-13") (pin "C") (pinfunction "C_C") (pintype "passive"))
      (node (ref "C5-14") (pin "C") (pinfunction "C_C") (pintype "passive"))
      (node (ref "C5-15") (pin "C") (pinfunction "C_C") (pintype "passive"))
      (node (ref "C5-9") (pin "C") (pinfunction "C_C") (pintype "passive"))
      (node (ref "C6-13") (pin "A") (pinfunction "A_A") (pintype "passive"))
      (node (ref "C7-13") (pin "A") (pinfunction "A_A") (pintype "passive"))
      (node (ref "C8-13") (pin "A") (pinfunction "A_A") (pintype "passive"))
      (node (ref "U1") (pin "11") (pinfunction "CB5_11") (pintype "bidirectional"))
    )
    (net (code "16") (name "/M_CB6") (class "Default")
      (node (ref "C2-13") (pin "A") (pinfunction "A_A") (pintype "passive"))
      (node (ref "C3-13") (pin "A") (pinfunction "A_A") (pintype "passive"))
      (node (ref "C4-13") (pin "A") (pinfunction "A_A") (pintype "passive"))
      (node (ref "C5-13") (pin "A") (pinfunction "A_A") (pintype "passive"))
      (node (ref "C6-10") (pin "C") (pinfunction "C_C") (pintype "passive"))
      (node (ref "C6-11") (pin "C") (pinfunction "C_C") (pintype "passive"))
      (node (ref "C6-12") (pin "C") (pinfunction "C_C") (pintype "passive"))
      (node (ref "C6-13") (pin "C") (pinfunction "C_C") (pintype "passive"))
      (node (ref "C6-14") (pin "C") (pinfunction "C_C") (pintype "passive"))
      (node (ref "C6-15") (pin "C") (pinfunction "C_C") (pintype "passive"))
      (node (ref "C6-9") (pin "C") (pinfunction "C_C") (pintype "passive"))
      (node (ref "C7-14") (pin "A") (pinfunction "A_A") (pintype "passive"))
      (node (ref "C8-14") (pin "A") (pinfunction "A_A") (pintype "passive"))
      (node (ref "U1") (pin "12") (pinfunction "CB6_12") (pintype "bidirectional"))
    )
    (net (code "17") (name "/M_CB7") (class "Default")
      (node (ref "C2-14") (pin "A") (pinfunction "A_A") (pintype "passive"))
      (node (ref "C3-14") (pin "A") (pinfunction "A_A") (pintype "passive"))
      (node (ref "C4-14") (pin "A") (pinfunction "A_A") (pintype "passive"))
      (node (ref "C5-14") (pin "A") (pinfunction "A_A") (pintype "passive"))
      (node (ref "C6-14") (pin "A") (pinfunction "A_A") (pintype "passive"))
      (node (ref "C7-10") (pin "C") (pinfunction "C_C") (pintype "passive"))
      (node (ref "C7-11") (pin "C") (pinfunction "C_C") (pintype "passive"))
      (node (ref "C7-12") (pin "C") (pinfunction "C_C") (pintype "passive"))
      (node (ref "C7-13") (pin "C") (pinfunction "C_C") (pintype "passive"))
      (node (ref "C7-14") (pin "C") (pinfunction "C_C") (pintype "passive"))
      (node (ref "C7-15") (pin "C") (pinfunction "C_C") (pintype "passive"))
      (node (ref "C7-9") (pin "C") (pinfunction "C_C") (pintype "passive"))
      (node (ref "C8-15") (pin "A") (pinfunction "A_A") (pintype "passive"))
      (node (ref "U1") (pin "13") (pinfunction "CB7_13") (pintype "bidirectional"))
    )
    (net (code "18") (name "/M_CB8") (class "Default")
      (node (ref "C2-15") (pin "A") (pinfunction "A_A") (pintype "passive"))
      (node (ref "C3-15") (pin "A") (pinfunction "A_A") (pintype "passive"))
      (node (ref "C4-15") (pin "A") (pinfunction "A_A") (pintype "passive"))
      (node (ref "C5-15") (pin "A") (pinfunction "A_A") (pintype "passive"))
      (node (ref "C6-15") (pin "A") (pinfunction "A_A") (pintype "passive"))
      (node (ref "C7-15") (pin "A") (pinfunction "A_A") (pintype "passive"))
      (node (ref "C8-10") (pin "C") (pinfunction "C_C") (pintype "passive"))
      (node (ref "C8-11") (pin "C") (pinfunction "C_C") (pintype "passive"))
      (node (ref "C8-12") (pin "C") (pinfunction "C_C") (pintype "passive"))
      (node (ref "C8-13") (pin "C") (pinfunction "C_C") (pintype "passive"))
      (node (ref "C8-14") (pin "C") (pinfunction "C_C") (pintype "passive"))
      (node (ref "C8-15") (pin "C") (pinfunction "C_C") (pintype "passive"))
      (node (ref "C8-9") (pin "C") (pinfunction "C_C") (pintype "passive"))
      (node (ref "U1") (pin "14") (pinfunction "CB8_14") (pintype "bidirectional"))
    )
    (net (code "19") (name "/M_INTB") (class "Default")
      (node (ref "U1") (pin "4") (pinfunction "INTB_4") (pintype "output"))
    )
    (net (code "20") (name "GND") (class "Default")
      (node (ref "C1") (pin "2") (pinfunction "2_2") (pintype "passive"))
      (node (ref "C2") (pin "2") (pinfunction "2_2") (pintype "passive"))
      (node (ref "C3") (pin "2") (pinfunction "2_2") (pintype "passive"))
      (node (ref "C4") (pin "2") (pinfunction "2_2") (pintype "passive"))
      (node (ref "C5") (pin "2") (pinfunction "2_2") (pintype "passive"))
      (node (ref "GND") (pin "TP") (pinfunction "TP_TP") (pintype "input"))
      (node (ref "K1") (pin "2") (pinfunction "P$2_2") (pintype "bidirectional"))
      (node (ref "R7") (pin "2") (pinfunction "2_2") (pintype "passive"))
      (node (ref "R8") (pin "1") (pinfunction "1_1") (pintype "passive"))
      (node (ref "S1") (pin "1") (pinfunction "NO_1") (pintype "bidirectional"))
      (node (ref "S2") (pin "1") (pinfunction "NO_1") (pintype "bidirectional"))
      (node (ref "U1") (pin "5") (pinfunction "GND_5") (pintype "power_in"))
      (node (ref "U1") (pin "THERMAL") (pinfunction "GND_THERMAL") (pintype "power_in"))
    )
    (net (code "21") (name "M_SCL") (class "Default")
      (node (ref "K1") (pin "4") (pinfunction "P$4_4") (pintype "bidirectional"))
      (node (ref "M_SCL") (pin "TP") (pinfunction "TP_TP") (pintype "input"))
      (node (ref "R6") (pin "1") (pinfunction "1_1") (pintype "passive"))
      (node (ref "U1") (pin "20") (pinfunction "SCL_20") (pintype "bidirectional"))
    )
    (net (code "22") (name "M_SDA") (class "Default")
      (node (ref "K1") (pin "3") (pinfunction "P$3_3") (pintype "bidirectional"))
      (node (ref "M_SDA") (pin "TP") (pinfunction "TP_TP") (pintype "input"))
      (node (ref "R4") (pin "1") (pinfunction "1_1") (pintype "passive"))
      (node (ref "U1") (pin "19") (pinfunction "SDA_19") (pintype "bidirectional"))
    )
    (net (code "23") (name "Net-(S1-COM)") (class "Default")
      (node (ref "C2") (pin "1") (pinfunction "1_1") (pintype "passive"))
      (node (ref "R1") (pin "1") (pinfunction "1_1") (pintype "passive"))
      (node (ref "R3") (pin "1") (pinfunction "1_1") (pintype "passive"))
      (node (ref "S1") (pin "2") (pinfunction "COM_2") (pintype "bidirectional"))
    )
    (net (code "24") (name "Net-(S2-COM)") (class "Default")
      (node (ref "C3") (pin "1") (pinfunction "1_1") (pintype "passive"))
      (node (ref "R2") (pin "1") (pinfunction "1_1") (pintype "passive"))
      (node (ref "R5") (pin "1") (pinfunction "1_1") (pintype "passive"))
      (node (ref "S2") (pin "2") (pinfunction "COM_2") (pintype "bidirectional"))
    )
    (net (code "25") (name "Net-(U1-R_EXT)") (class "Default")
      (node (ref "R8") (pin "2") (pinfunction "2_2") (pintype "passive"))
      (node (ref "U1") (pin "6") (pinfunction "R_EXT_6") (pintype "bidirectional"))
    )
    (net (code "26") (name "S_DOWN") (class "Default")
      (node (ref "K1") (pin "6") (pinfunction "P$6_6") (pintype "bidirectional"))
      (node (ref "R5") (pin "2") (pinfunction "2_2") (pintype "passive"))
      (node (ref "S_DOWN") (pin "TP") (pinfunction "TP_TP") (pintype "input"))
    )
    (net (code "27") (name "S_UP") (class "Default")
      (node (ref "K1") (pin "5") (pinfunction "P$5_5") (pintype "bidirectional"))
      (node (ref "R3") (pin "2") (pinfunction "2_2") (pintype "passive"))
      (node (ref "S_UP") (pin "TP") (pinfunction "TP_TP") (pintype "input"))
    )
    (net (code "28") (name "VCC") (class "Default")
      (node (ref "C1") (pin "1") (pinfunction "1_1") (pintype "passive"))
      (node (ref "C4") (pin "1") (pinfunction "1_1") (pintype "passive"))
      (node (ref "C5") (pin "1") (pinfunction "1_1") (pintype "passive"))
      (node (ref "K1") (pin "1") (pinfunction "P$1_1") (pintype "bidirectional"))
      (node (ref "R1") (pin "2") (pinfunction "2_2") (pintype "passive"))
      (node (ref "R2") (pin "2") (pinfunction "2_2") (pintype "passive"))
      (node (ref "R4") (pin "2") (pinfunction "2_2") (pintype "passive"))
      (node (ref "R6") (pin "2") (pinfunction "2_2") (pintype "passive"))
      (node (ref "U1") (pin "2") (pinfunction "VCC_2") (pintype "power_in"))
      (node (ref "U1") (pin "3") (pinfunction "SHUTDOWN_3") (pintype "input"))
      (node (ref "VCC") (pin "TP") (pinfunction "TP_TP") (pintype "input"))
    )
    (net (code "29") (name "unconnected-(U1-AUDIOIN-Pad17)") (class "Default")
      (node (ref "U1") (pin "17") (pinfunction "AUDIOIN_17") (pintype "input"))
    )
    (net (code "30") (name "unconnected-(U1-CB9-Pad15)") (class "Default")
      (node (ref "U1") (pin "15") (pinfunction "CB9_15") (pintype "bidirectional"))
    )
    (net (code "31") (name "unconnected-(U1-C_FILT-Pad16)") (class "Default")
      (node (ref "U1") (pin "16") (pinfunction "C_FILT_16") (pintype "bidirectional"))
    )
  )
)
